# Iot_switch.net
KiCad netlist of a schematic drawn in Altium Designer
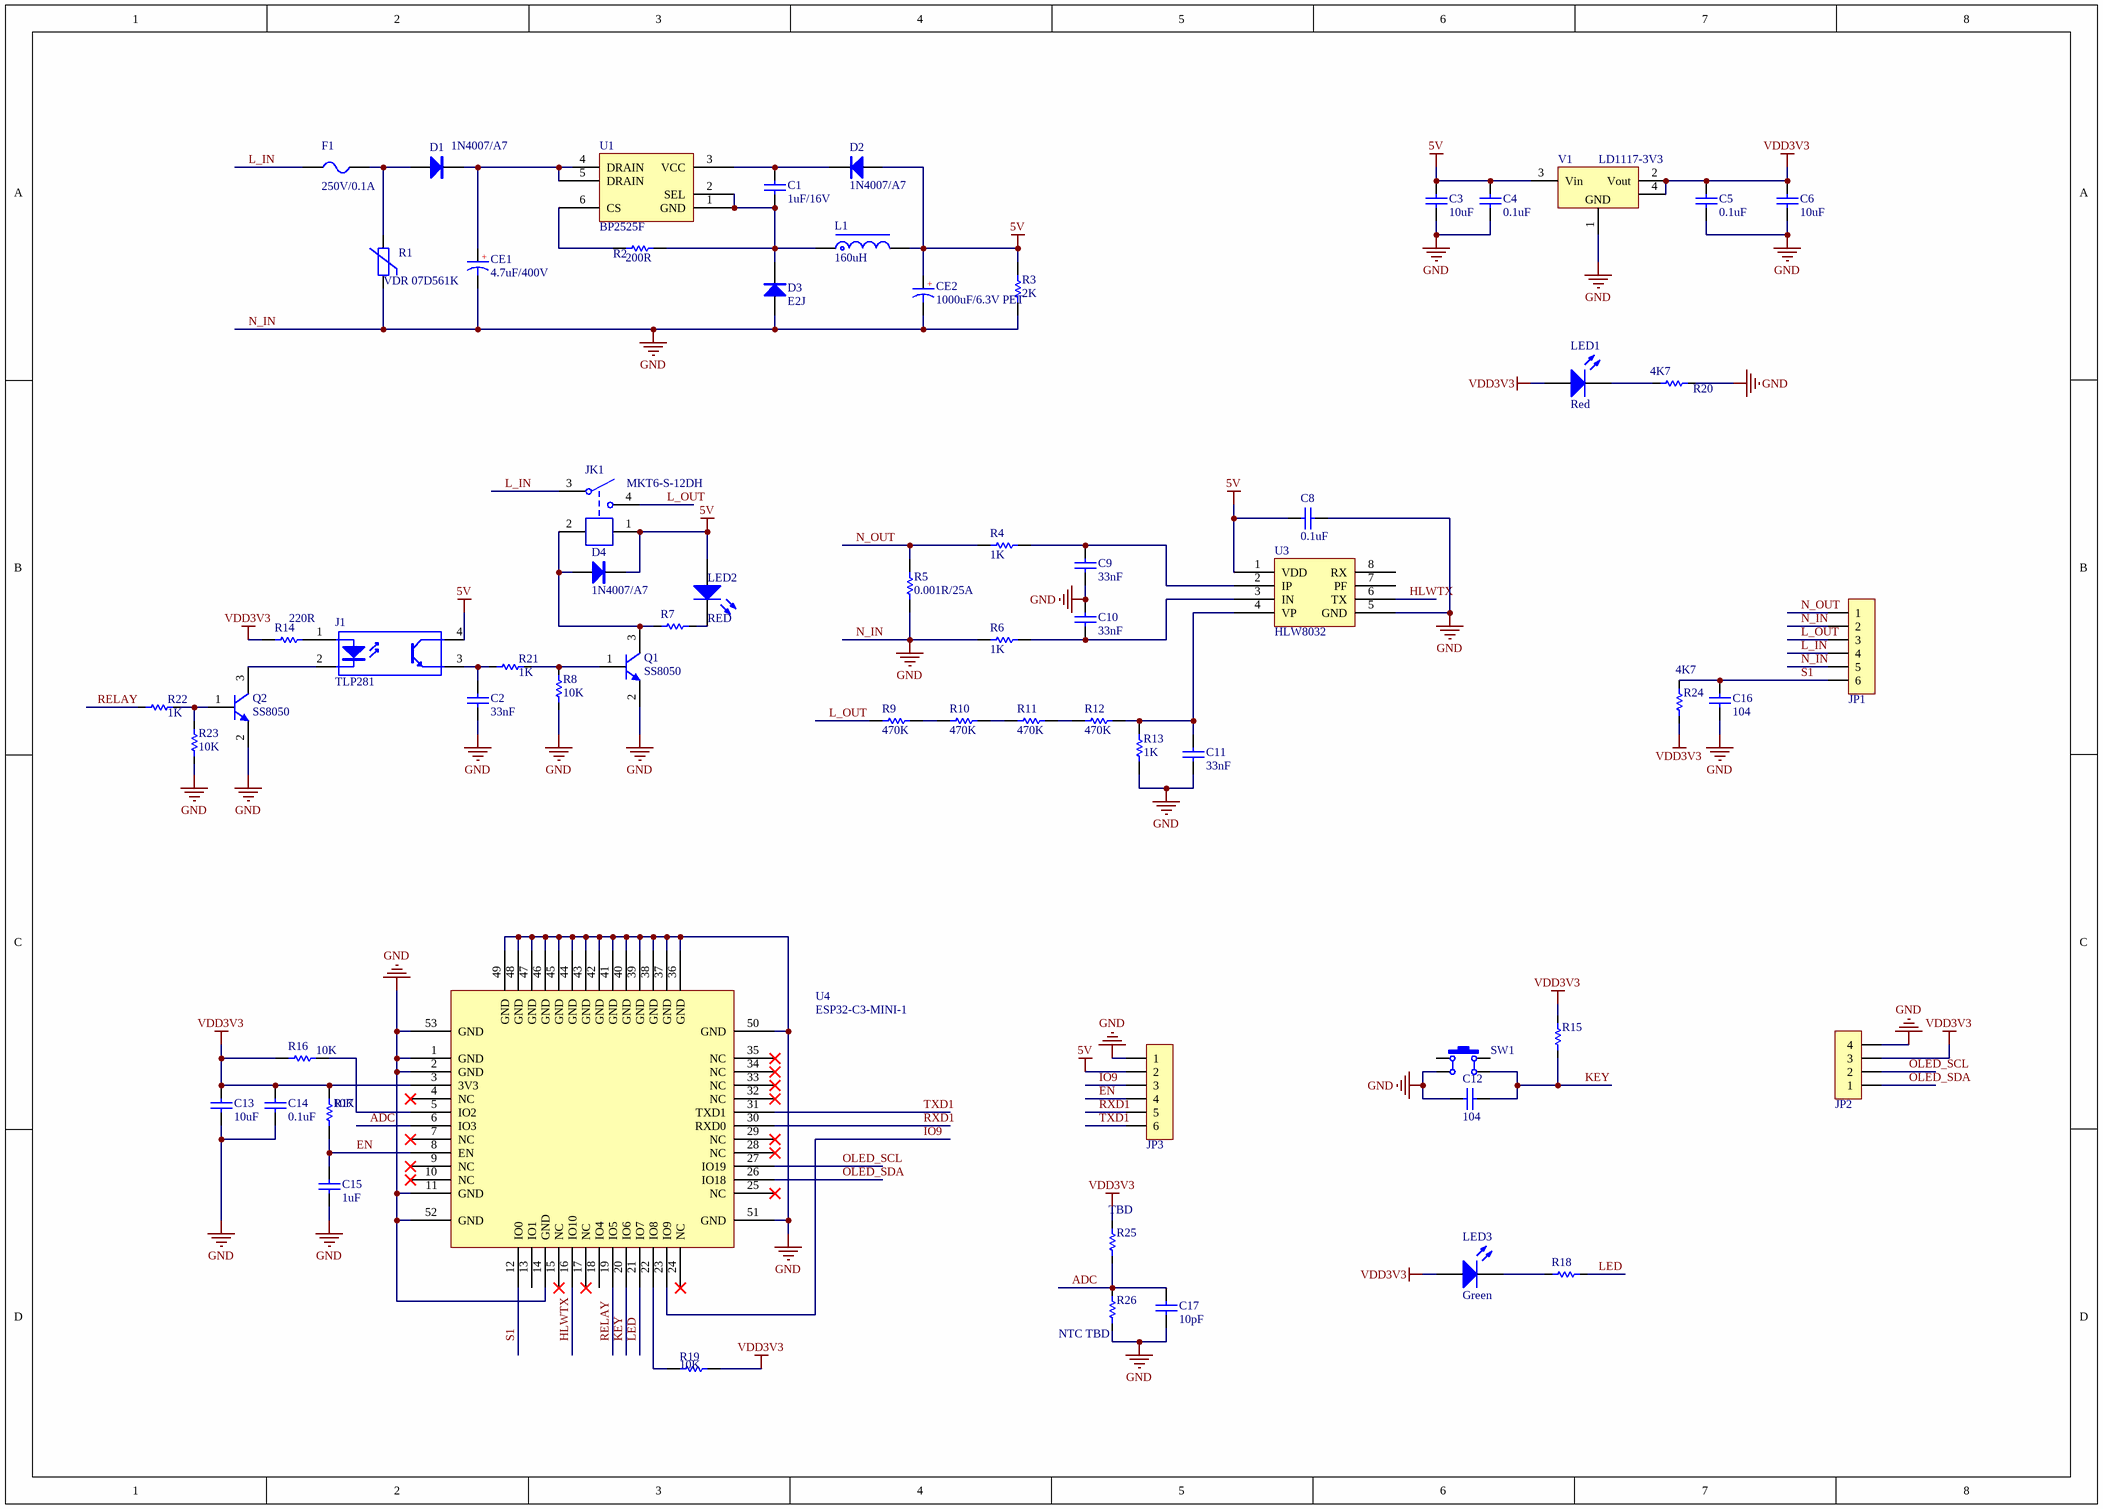
[diagram p0: Iot_switch.SchDoc]

(export (version "E")
  (design (tool "Eeschema 10.0.6"))
  (components
    (comp (ref "C1")
      (value "1uF/16V")
      (footprint "C0805_L")
      (fields (field (name "PUBLISHER") "Altium Limited"))
      (libsource (lib "Miscellaneous Devices") (part "Cap"))
    )
    (comp (ref "C2")
      (value "33nF")
      (footprint "C0603_L")
      (description "贴片电容/MLCC电容")
      (libsource (lib "0.1 - 电阻-电容-电感-保险丝-晶振-晶体-磁珠-电位器-法拉电容-馈通电容") (part "C"))
    )
    (comp (ref "C3")
      (value "10uF")
      (footprint "C0603_L")
      (description "贴片电容/MLCC电容")
      (libsource (lib "0.1 - 电阻-电容-电感-保险丝-晶振-晶体-磁珠-电位器-法拉电容-馈通电容") (part "C"))
    )
    (comp (ref "C4")
      (value "0.1uF")
      (footprint "C0603_L")
      (description "贴片电容/MLCC电容")
      (libsource (lib "0.1 - 电阻-电容-电感-保险丝-晶振-晶体-磁珠-电位器-法拉电容-馈通电容") (part "C"))
    )
    (comp (ref "C5")
      (value "0.1uF")
      (footprint "C0603_L")
      (description "贴片电容/MLCC电容")
      (libsource (lib "0.1 - 电阻-电容-电感-保险丝-晶振-晶体-磁珠-电位器-法拉电容-馈通电容") (part "C"))
    )
    (comp (ref "C6")
      (value "10uF")
      (footprint "C0603_L")
      (description "贴片电容/MLCC电容")
      (libsource (lib "0.1 - 电阻-电容-电感-保险丝-晶振-晶体-磁珠-电位器-法拉电容-馈通电容") (part "C"))
    )
    (comp (ref "C8")
      (value "0.1uF")
      (footprint "C0603_L")
      (description "贴片电容/MLCC电容")
      (libsource (lib "0.1 - 电阻-电容-电感-保险丝-晶振-晶体-磁珠-电位器-法拉电容-馈通电容") (part "C"))
    )
    (comp (ref "C9")
      (value "33nF")
      (footprint "C0603_L")
      (description "贴片电容/MLCC电容")
      (libsource (lib "0.1 - 电阻-电容-电感-保险丝-晶振-晶体-磁珠-电位器-法拉电容-馈通电容") (part "C"))
    )
    (comp (ref "C10")
      (value "33nF")
      (footprint "C0603_L")
      (description "贴片电容/MLCC电容")
      (libsource (lib "0.1 - 电阻-电容-电感-保险丝-晶振-晶体-磁珠-电位器-法拉电容-馈通电容") (part "C"))
    )
    (comp (ref "C11")
      (value "33nF")
      (footprint "C0805_L")
      (description "贴片电容/MLCC电容")
      (libsource (lib "0.1 - 电阻-电容-电感-保险丝-晶振-晶体-磁珠-电位器-法拉电容-馈通电容") (part "C"))
    )
    (comp (ref "C12")
      (value "104")
      (footprint "C0603_L")
      (description "贴片电容/MLCC电容")
      (libsource (lib "0.1 - 电阻-电容-电感-保险丝-晶振-晶体-磁珠-电位器-法拉电容-馈通电容") (part "C"))
    )
    (comp (ref "C13")
      (value "10uF")
      (footprint "C0603_L")
      (description "贴片电容/MLCC电容")
      (libsource (lib "0.1 - 电阻-电容-电感-保险丝-晶振-晶体-磁珠-电位器-法拉电容-馈通电容") (part "C"))
    )
    (comp (ref "C14")
      (value "0.1uF")
      (footprint "C0603_L")
      (description "贴片电容/MLCC电容")
      (libsource (lib "0.1 - 电阻-电容-电感-保险丝-晶振-晶体-磁珠-电位器-法拉电容-馈通电容") (part "C"))
    )
    (comp (ref "C15")
      (value "1uF")
      (footprint "C0603_L")
      (description "贴片电容/MLCC电容")
      (libsource (lib "0.1 - 电阻-电容-电感-保险丝-晶振-晶体-磁珠-电位器-法拉电容-馈通电容") (part "C"))
    )
    (comp (ref "C16")
      (value "104")
      (footprint "C0603_L")
      (description "贴片电容/MLCC电容")
      (libsource (lib "0.1 - 电阻-电容-电感-保险丝-晶振-晶体-磁珠-电位器-法拉电容-馈通电容") (part "C"))
    )
    (comp (ref "C17")
      (value "10pF")
      (footprint "C0603_L")
      (description "贴片电容/MLCC电容")
      (libsource (lib "0.1 - 电阻-电容-电感-保险丝-晶振-晶体-磁珠-电位器-法拉电容-馈通电容") (part "C"))
    )
    (comp (ref "CE1")
      (value "4.7uF/400V")
      (footprint "CE-3.5*8*11.5")
      (description "直插电解电容")
      (libsource (lib "0.1 - 电阻-电容-电感-保险丝-晶振-晶体-磁珠-电位器-法拉电容-馈通电容") (part "CE"))
    )
    (comp (ref "CE2")
      (value "1000uF/6.3V PET")
      (footprint "CE-3.5*8*11.5")
      (description "直插电解电容")
      (libsource (lib "0.1 - 电阻-电容-电感-保险丝-晶振-晶体-磁珠-电位器-法拉电容-馈通电容") (part "CE"))
    )
    (comp (ref "D1")
      (value "1N4007/A7")
      (footprint "SOD-123")
      (description "整流二极管")
      (libsource (lib "0.2 - 二极管-TVS-ESD-整流桥-放电管") (part "1N4007"))
    )
    (comp (ref "D2")
      (value "1N4007/A7")
      (footprint "SOD-123")
      (description "整流二极管")
      (libsource (lib "0.2 - 二极管-TVS-ESD-整流桥-放电管") (part "1N4007"))
    )
    (comp (ref "D3")
      (value "E2J")
      (footprint "SOD-123")
      (description "整流二极管")
      (libsource (lib "0.2 - 二极管-TVS-ESD-整流桥-放电管") (part "1N4007"))
    )
    (comp (ref "D4")
      (value "1N4007/A7")
      (footprint "SOD-123")
      (description "整流二极管")
      (libsource (lib "0.2 - 二极管-TVS-ESD-整流桥-放电管") (part "1N4007"))
    )
    (comp (ref "F1")
      (value "250V/0.1A")
      (footprint "FUSE 4x16_V")
      (description "4*16保险丝")
      (libsource (lib "0.1 - 电阻-电容-电感-保险丝-晶振-晶体-磁珠-电位器-法拉电容-馈通电容") (part "FUSE-4x16"))
    )
    (comp (ref "J1")
      (value "TLP281")
      (footprint "SOP4")
      (description "光耦")
      (libsource (lib "0.3 - LED发光二极管-IR二极管_接收管-光耦") (part "TLP281"))
    )
    (comp (ref "JK1")
      (value "MKT6-S-12DH")
      (footprint "MKT6-S-12DH")
      (description "12V一组常开")
      (libsource (lib "1.4 - 继电器-变压器") (part "MKT6-S-12DH"))
    )
    (comp (ref "JP1")
      (value "HDR-1X6")
      (footprint "KF128-5.08-6P")
      (description "6P接插件")
      (libsource (lib "6.1 - 5.08mm连接器(KF128-KF2EDGK-KF2EDGVHM-5.08)") (part "Header 6"))
    )
    (comp (ref "JP2")
      (value "HDR-1X4")
      (footprint "HDR2.54-M-LI-4P")
      (description "4P接插件")
      (libsource (lib "5.5 - 2.54mm连接器(KF2EDGK_XH2.54_2.54排针排母)") (part "Header 4"))
    )
    (comp (ref "JP3")
      (value "HDR-1X6")
      (footprint "HDR2.54-LI-6P")
      (description "6P接插件")
      (libsource (lib "5.5 - 2.54mm连接器(KF2EDGK_XH2.54_2.54排针排母)") (part "Header 6"))
    )
    (comp (ref "L1")
      (value "160uH")
      (footprint "PK0608")
      (description "工字电感")
      (libsource (lib "0.1 - 电阻-电容-电感-保险丝-晶振-晶体-磁珠-电位器-法拉电容-馈通电容") (part "L-PK"))
    )
    (comp (ref "LED1")
      (value "Red")
      (footprint "LED0603_R")
      (description "贴片LED")
      (libsource (lib "0.3 - LED发光二极管-IR二极管_接收管-光耦") (part "LED"))
    )
    (comp (ref "LED2")
      (value "RED")
      (footprint "LED0603_R")
      (description "贴片LED")
      (libsource (lib "0.3 - LED发光二极管-IR二极管_接收管-光耦") (part "LED"))
    )
    (comp (ref "LED3")
      (value "Green")
      (footprint "LED0603_G")
      (description "贴片LED")
      (libsource (lib "0.3 - LED发光二极管-IR二极管_接收管-光耦") (part "LED"))
    )
    (comp (ref "Q1")
      (value "SS8050")
      (footprint "SOT23-3M")
      (description "NPN三极管")
      (libsource (lib "0.4 - 三极管-场效应管-可控硅") (part "BCP68"))
    )
    (comp (ref "Q2")
      (value "SS8050")
      (footprint "SOT23-3M")
      (description "NPN三极管")
      (libsource (lib "0.4 - 三极管-场效应管-可控硅") (part "BCP68"))
    )
    (comp (ref "R1")
      (value "VDR 07D561K")
      (footprint "VDR 9D-4.5")
      (description "压敏电阻")
      (libsource (lib "0.1 - 电阻-电容-电感-保险丝-晶振-晶体-磁珠-电位器-法拉电容-馈通电容") (part "R_VSR"))
    )
    (comp (ref "R2")
      (value "200R")
      (footprint "R0603_L")
      (description "Resistor")
      (fields (field (name "PUBLISHER") "Altium Limited"))
      (libsource (lib "Miscellaneous Devices") (part "Res1"))
    )
    (comp (ref "R3")
      (value "2K")
      (footprint "R0603_L")
      (description "Resistor")
      (fields (field (name "PUBLISHER") "Altium Limited"))
      (libsource (lib "Miscellaneous Devices") (part "Res1"))
    )
    (comp (ref "R4")
      (value "1K")
      (footprint "R0603_L")
      (description "Resistor")
      (fields (field (name "PUBLISHER") "Altium Limited"))
      (libsource (lib "Miscellaneous Devices") (part "Res1"))
    )
    (comp (ref "R5")
      (value "0.001R/25A")
      (footprint "R2512_L")
      (description "Resistor")
      (fields (field (name "PUBLISHER") "Altium Limited"))
      (libsource (lib "Miscellaneous Devices") (part "Res1"))
    )
    (comp (ref "R6")
      (value "1K")
      (footprint "R0603_L")
      (description "Resistor")
      (fields (field (name "PUBLISHER") "Altium Limited"))
      (libsource (lib "Miscellaneous Devices") (part "Res1"))
    )
    (comp (ref "R7")
      (value "4K7")
      (footprint "R0603_L")
      (description "贴片电阻")
      (fields (field (name "PUBLISHER") "Altium Limited"))
      (libsource (lib "Devices") (part "Res1"))
    )
    (comp (ref "R8")
      (value "10K")
      (footprint "R0603_L")
      (description "贴片电阻")
      (fields (field (name "PUBLISHER") "Altium Limited"))
      (libsource (lib "Devices") (part "Res1"))
    )
    (comp (ref "R9")
      (value "470K")
      (footprint "R0805_L")
      (description "Resistor")
      (fields (field (name "PUBLISHER") "Altium Limited"))
      (libsource (lib "Miscellaneous Devices") (part "Res1"))
    )
    (comp (ref "R10")
      (value "470K")
      (footprint "R0805_L")
      (description "Resistor")
      (fields (field (name "PUBLISHER") "Altium Limited"))
      (libsource (lib "Miscellaneous Devices") (part "Res1"))
    )
    (comp (ref "R11")
      (value "470K")
      (footprint "R0805_L")
      (description "Resistor")
      (fields (field (name "PUBLISHER") "Altium Limited"))
      (libsource (lib "Miscellaneous Devices") (part "Res1"))
    )
    (comp (ref "R12")
      (value "470K")
      (footprint "R0805_L")
      (description "Resistor")
      (fields (field (name "PUBLISHER") "Altium Limited"))
      (libsource (lib "Miscellaneous Devices") (part "Res1"))
    )
    (comp (ref "R13")
      (value "1K")
      (footprint "R0805_l")
      (description "Resistor")
      (fields (field (name "PUBLISHER") "Altium Limited"))
      (libsource (lib "Miscellaneous Devices") (part "Res1"))
    )
    (comp (ref "R14")
      (value "220R")
      (footprint "R0603_l")
      (description "Resistor")
      (fields (field (name "PUBLISHER") "Altium Limited"))
      (libsource (lib "Miscellaneous Devices") (part "Res1"))
    )
    (comp (ref "R15")
      (value "10K")
      (footprint "R0603_L")
      (description "贴片电阻")
      (fields (field (name "PUBLISHER") "Altium Limited"))
      (libsource (lib "Devices") (part "Res1"))
    )
    (comp (ref "R16")
      (value "10K")
      (footprint "R0603_L")
      (description "Resistor")
      (fields (field (name "PUBLISHER") "Altium Limited"))
      (libsource (lib "Miscellaneous Devices") (part "Res1"))
    )
    (comp (ref "R17")
      (value "10K")
      (footprint "R0603_L")
      (description "Resistor")
      (fields (field (name "PUBLISHER") "Altium Limited"))
      (libsource (lib "Miscellaneous Devices") (part "Res1"))
    )
    (comp (ref "R18")
      (value "4K7")
      (footprint "R0603_L")
      (description "贴片电阻")
      (fields (field (name "PUBLISHER") "Altium Limited"))
      (libsource (lib "Devices") (part "Res1"))
    )
    (comp (ref "R19")
      (value "10K")
      (footprint "R0603_L")
      (description "Resistor")
      (fields (field (name "PUBLISHER") "Altium Limited"))
      (libsource (lib "Miscellaneous Devices") (part "Res1"))
    )
    (comp (ref "R20")
      (value "4K7")
      (footprint "R0603_L")
      (description "贴片电阻")
      (fields (field (name "PUBLISHER") "Altium Limited"))
      (libsource (lib "Devices") (part "Res1"))
    )
    (comp (ref "R21")
      (value "1K")
      (footprint "R0603_L")
      (description "贴片电阻")
      (fields (field (name "PUBLISHER") "Altium Limited"))
      (libsource (lib "Devices") (part "Res1"))
    )
    (comp (ref "R22")
      (value "1K")
      (footprint "R0603_L")
      (description "贴片电阻")
      (fields (field (name "PUBLISHER") "Altium Limited"))
      (libsource (lib "Devices") (part "Res1"))
    )
    (comp (ref "R23")
      (value "10K")
      (footprint "R0603_L")
      (description "贴片电阻")
      (fields (field (name "PUBLISHER") "Altium Limited"))
      (libsource (lib "Devices") (part "Res1"))
    )
    (comp (ref "R24")
      (value "4K7")
      (footprint "R0603_L")
      (description "贴片电阻")
      (fields (field (name "PUBLISHER") "Altium Limited"))
      (libsource (lib "Devices") (part "Res1"))
    )
    (comp (ref "R25")
      (value "TBD")
      (footprint "R0603_L")
      (description "贴片电阻")
      (fields (field (name "PUBLISHER") "Altium Limited"))
      (libsource (lib "Devices") (part "Res1"))
    )
    (comp (ref "R26")
      (value "NTC TBD")
      (footprint "R0603_L")
      (description "贴片电阻")
      (fields (field (name "PUBLISHER") "Altium Limited"))
      (libsource (lib "Devices") (part "Res1"))
    )
    (comp (ref "SW1")
      (value "3*4*2.5")
      (footprint "SW-SMD-4.2x3.2_4P")
      (description "贴片4脚轻触开关")
      (libsource (lib "0.5 - 按键_开关_蜂鸣器_电池_测试点_Mark点_铜柱") (part "SW SMD-3*4*2.5"))
    )
    (comp (ref "U1") (value "BP2525F") (footprint "SOT33-5") (libsource (lib "iot switch") (part "BP2525X")))
    (comp (ref "U3") (value "HLW8032") (footprint "SOP_8") (libsource (lib "iot switch") (part "HLW8032")))
    (comp (ref "U4")
      (value "ESP32-C3-MINI-1")
      (footprint "ESP32-C3-MINI-1")
      (libsource (lib "iot switch") (part "ESP32-C3-MINI-1"))
    )
    (comp (ref "V1")
      (value "LD1117-3V3")
      (footprint "SOT223_L")
      (description "三端稳压芯片")
      (libsource (lib "0.7 - 电源类芯片") (part "LD1117"))
    )
  )
  (nets
    (net (code "1") (name "/ADC") (class "Default")
      (node (ref "C17") (pin "1") (pinfunction "1_1") (pintype "passive"))
      (node (ref "R25") (pin "1") (pinfunction "TOP_1") (pintype "passive"))
      (node (ref "R26") (pin "2") (pinfunction "BOT_2") (pintype "passive"))
      (node (ref "U4") (pin "6") (pinfunction "IO3_6") (pintype "passive"))
    )
    (net (code "2") (name "/EN") (class "Default")
      (node (ref "C15") (pin "2") (pinfunction "2_2") (pintype "passive"))
      (node (ref "JP3") (pin "4") (pinfunction "4_4") (pintype "passive"))
      (node (ref "R17") (pin "1") (pinfunction "1_1") (pintype "passive"))
      (node (ref "U4") (pin "8") (pinfunction "EN_8") (pintype "passive"))
    )
    (net (code "3") (name "/HLWTX") (class "Default")
      (node (ref "U3") (pin "6") (pinfunction "TX_6") (pintype "passive"))
      (node (ref "U4") (pin "16") (pinfunction "IO10_16") (pintype "passive"))
    )
    (net (code "4") (name "/IO9") (class "Default")
      (node (ref "JP3") (pin "3") (pinfunction "3_3") (pintype "passive"))
      (node (ref "U4") (pin "23") (pinfunction "IO9_23") (pintype "passive"))
    )
    (net (code "5") (name "/KEY") (class "Default")
      (node (ref "C12") (pin "2") (pinfunction "2_2") (pintype "passive"))
      (node (ref "R15") (pin "1") (pinfunction "TOP_1") (pintype "passive"))
      (node (ref "SW1") (pin "3") (pinfunction "3_3") (pintype "passive"))
      (node (ref "U4") (pin "20") (pinfunction "IO6_20") (pintype "passive"))
    )
    (net (code "6") (name "/LED") (class "Default")
      (node (ref "R18") (pin "2") (pinfunction "BOT_2") (pintype "passive"))
      (node (ref "U4") (pin "21") (pinfunction "IO7_21") (pintype "passive"))
    )
    (net (code "7") (name "/L_IN") (class "Default")
      (node (ref "F1") (pin "2") (pinfunction "2_2") (pintype "passive"))
      (node (ref "JK1") (pin "3") (pinfunction "3_3") (pintype "passive"))
      (node (ref "JP1") (pin "4") (pinfunction "4_4") (pintype "passive"))
    )
    (net (code "8") (name "/L_OUT") (class "Default")
      (node (ref "JK1") (pin "4") (pinfunction "4_4") (pintype "passive"))
      (node (ref "JP1") (pin "3") (pinfunction "3_3") (pintype "passive"))
      (node (ref "R9") (pin "2") (pinfunction "2_2") (pintype "passive"))
    )
    (net (code "9") (name "/N_OUT") (class "Default")
      (node (ref "JP1") (pin "1") (pinfunction "1_1") (pintype "passive"))
      (node (ref "R4") (pin "2") (pinfunction "2_2") (pintype "passive"))
      (node (ref "R5") (pin "1") (pinfunction "1_1") (pintype "passive"))
    )
    (net (code "10") (name "/OLED_SCL") (class "Default")
      (node (ref "JP2") (pin "2") (pinfunction "2_2") (pintype "passive"))
      (node (ref "U4") (pin "27") (pinfunction "IO19_27") (pintype "passive"))
    )
    (net (code "11") (name "/OLED_SDA") (class "Default")
      (node (ref "JP2") (pin "1") (pinfunction "1_1") (pintype "passive"))
      (node (ref "U4") (pin "26") (pinfunction "IO18_26") (pintype "passive"))
    )
    (net (code "12") (name "/RELAY") (class "Default")
      (node (ref "R22") (pin "1") (pinfunction "TOP_1") (pintype "passive"))
      (node (ref "U4") (pin "19") (pinfunction "IO5_19") (pintype "passive"))
    )
    (net (code "13") (name "/RXD1") (class "Default")
      (node (ref "JP3") (pin "5") (pinfunction "5_5") (pintype "passive"))
      (node (ref "U4") (pin "30") (pinfunction "RXD0_30") (pintype "passive"))
    )
    (net (code "14") (name "/S1") (class "Default")
      (node (ref "C16") (pin "2") (pinfunction "2_2") (pintype "passive"))
      (node (ref "JP1") (pin "6") (pinfunction "6_6") (pintype "passive"))
      (node (ref "R24") (pin "2") (pinfunction "BOT_2") (pintype "passive"))
      (node (ref "U4") (pin "12") (pinfunction "IO0_12") (pintype "passive"))
    )
    (net (code "15") (name "/TXD1") (class "Default")
      (node (ref "JP3") (pin "6") (pinfunction "6_6") (pintype "passive"))
      (node (ref "U4") (pin "31") (pinfunction "TXD1_31") (pintype "passive"))
    )
    (net (code "16") (name "5V") (class "Default")
      (node (ref "C3") (pin "2") (pinfunction "2_2") (pintype "passive"))
      (node (ref "C4") (pin "2") (pinfunction "2_2") (pintype "passive"))
      (node (ref "C8") (pin "2") (pinfunction "2_2") (pintype "passive"))
      (node (ref "CE2") (pin "1") (pinfunction "1_1") (pintype "passive"))
      (node (ref "D2") (pin "1") (pinfunction "A_1") (pintype "passive"))
      (node (ref "D4") (pin "2") (pinfunction "K_2") (pintype "passive"))
      (node (ref "J1") (pin "4") (pinfunction "C_4") (pintype "passive"))
      (node (ref "JK1") (pin "1") (pinfunction "1_1") (pintype "passive"))
      (node (ref "JP3") (pin "2") (pinfunction "2_2") (pintype "passive"))
      (node (ref "L1") (pin "2") (pinfunction "2_2") (pintype "passive"))
      (node (ref "LED2") (pin "1") (pinfunction "A_1") (pintype "passive"))
      (node (ref "R3") (pin "2") (pinfunction "2_2") (pintype "passive"))
      (node (ref "U3") (pin "1") (pinfunction "VDD_1") (pintype "passive"))
      (node (ref "V1") (pin "3") (pinfunction "Vin_3") (pintype "passive"))
    )
    (net (code "17") (name "GND") (class "Default")
      (node (ref "C10") (pin "1") (pinfunction "1_1") (pintype "passive"))
      (node (ref "C11") (pin "2") (pinfunction "2_2") (pintype "passive"))
      (node (ref "C12") (pin "1") (pinfunction "1_1") (pintype "passive"))
      (node (ref "C13") (pin "1") (pinfunction "1_1") (pintype "passive"))
      (node (ref "C14") (pin "1") (pinfunction "1_1") (pintype "passive"))
      (node (ref "C15") (pin "1") (pinfunction "1_1") (pintype "passive"))
      (node (ref "C16") (pin "1") (pinfunction "1_1") (pintype "passive"))
      (node (ref "C17") (pin "2") (pinfunction "2_2") (pintype "passive"))
      (node (ref "C2") (pin "2") (pinfunction "2_2") (pintype "passive"))
      (node (ref "C3") (pin "1") (pinfunction "1_1") (pintype "passive"))
      (node (ref "C4") (pin "1") (pinfunction "1_1") (pintype "passive"))
      (node (ref "C5") (pin "1") (pinfunction "1_1") (pintype "passive"))
      (node (ref "C6") (pin "1") (pinfunction "1_1") (pintype "passive"))
      (node (ref "C8") (pin "1") (pinfunction "1_1") (pintype "passive"))
      (node (ref "C9") (pin "2") (pinfunction "2_2") (pintype "passive"))
      (node (ref "CE1") (pin "2") (pinfunction "2_2") (pintype "passive"))
      (node (ref "CE2") (pin "2") (pinfunction "2_2") (pintype "passive"))
      (node (ref "D3") (pin "1") (pinfunction "A_1") (pintype "passive"))
      (node (ref "JP1") (pin "2") (pinfunction "2_2") (pintype "passive"))
      (node (ref "JP1") (pin "5") (pinfunction "5_5") (pintype "passive"))
      (node (ref "JP2") (pin "4") (pinfunction "4_4") (pintype "passive"))
      (node (ref "JP3") (pin "1") (pinfunction "1_1") (pintype "passive"))
      (node (ref "Q1") (pin "2") (pinfunction "E_2") (pintype "passive"))
      (node (ref "Q2") (pin "2") (pinfunction "E_2") (pintype "passive"))
      (node (ref "R1") (pin "1") (pinfunction "1_1") (pintype "passive"))
      (node (ref "R13") (pin "2") (pinfunction "2_2") (pintype "passive"))
      (node (ref "R20") (pin "2") (pinfunction "BOT_2") (pintype "passive"))
      (node (ref "R23") (pin "2") (pinfunction "BOT_2") (pintype "passive"))
      (node (ref "R26") (pin "1") (pinfunction "TOP_1") (pintype "passive"))
      (node (ref "R3") (pin "1") (pinfunction "1_1") (pintype "passive"))
      (node (ref "R5") (pin "2") (pinfunction "2_2") (pintype "passive"))
      (node (ref "R6") (pin "2") (pinfunction "2_2") (pintype "passive"))
      (node (ref "R8") (pin "2") (pinfunction "BOT_2") (pintype "passive"))
      (node (ref "SW1") (pin "4") (pinfunction "4_4") (pintype "passive"))
      (node (ref "U3") (pin "5") (pinfunction "GND_5") (pintype "passive"))
      (node (ref "U4") (pin "1") (pinfunction "GND_1") (pintype "passive"))
      (node (ref "U4") (pin "11") (pinfunction "GND_11") (pintype "passive"))
      (node (ref "U4") (pin "14") (pinfunction "GND_14") (pintype "passive"))
      (node (ref "U4") (pin "2") (pinfunction "GND_2") (pintype "passive"))
      (node (ref "U4") (pin "36") (pinfunction "GND_36") (pintype "passive"))
      (node (ref "U4") (pin "37") (pinfunction "GND_37") (pintype "passive"))
      (node (ref "U4") (pin "38") (pinfunction "GND_38") (pintype "passive"))
      (node (ref "U4") (pin "39") (pinfunction "GND_39") (pintype "passive"))
      (node (ref "U4") (pin "40") (pinfunction "GND_40") (pintype "passive"))
      (node (ref "U4") (pin "41") (pinfunction "GND_41") (pintype "passive"))
      (node (ref "U4") (pin "42") (pinfunction "GND_42") (pintype "passive"))
      (node (ref "U4") (pin "43") (pinfunction "GND_43") (pintype "passive"))
      (node (ref "U4") (pin "44") (pinfunction "GND_44") (pintype "passive"))
      (node (ref "U4") (pin "45") (pinfunction "GND_45") (pintype "passive"))
      (node (ref "U4") (pin "46") (pinfunction "GND_46") (pintype "passive"))
      (node (ref "U4") (pin "47") (pinfunction "GND_47") (pintype "passive"))
      (node (ref "U4") (pin "48") (pinfunction "GND_48") (pintype "passive"))
      (node (ref "U4") (pin "49") (pinfunction "GND_49") (pintype "passive"))
      (node (ref "U4") (pin "50") (pinfunction "GND_50") (pintype "passive"))
      (node (ref "U4") (pin "51") (pinfunction "GND_51") (pintype "passive"))
      (node (ref "U4") (pin "52") (pinfunction "GND_52") (pintype "passive"))
      (node (ref "U4") (pin "53") (pinfunction "GND_53") (pintype "passive"))
      (node (ref "V1") (pin "1") (pinfunction "GND_1") (pintype "passive"))
    )
    (net (code "18") (name "Net-(D1-A)") (class "Default")
      (node (ref "D1") (pin "1") (pinfunction "A_1") (pintype "passive"))
      (node (ref "F1") (pin "1") (pinfunction "1_1") (pintype "passive"))
      (node (ref "R1") (pin "2") (pinfunction "2_2") (pintype "passive"))
    )
    (net (code "19") (name "Net-(D1-K)") (class "Default")
      (node (ref "CE1") (pin "1") (pinfunction "1_1") (pintype "passive"))
      (node (ref "D1") (pin "2") (pinfunction "K_2") (pintype "passive"))
      (node (ref "U1") (pin "4") (pinfunction "DRAIN_4") (pintype "passive"))
      (node (ref "U1") (pin "5") (pinfunction "DRAIN_5") (pintype "passive"))
    )
    (net (code "20") (name "Net-(D2-K)") (class "Default")
      (node (ref "C1") (pin "2") (pinfunction "2_2") (pintype "passive"))
      (node (ref "D2") (pin "2") (pinfunction "K_2") (pintype "passive"))
      (node (ref "U1") (pin "3") (pinfunction "VCC_3") (pintype "passive"))
    )
    (net (code "21") (name "Net-(D3-K)") (class "Default")
      (node (ref "C1") (pin "1") (pinfunction "1_1") (pintype "passive"))
      (node (ref "D3") (pin "2") (pinfunction "K_2") (pintype "passive"))
      (node (ref "L1") (pin "1") (pinfunction "1_1") (pintype "passive"))
      (node (ref "R2") (pin "1") (pinfunction "1_1") (pintype "passive"))
      (node (ref "U1") (pin "1") (pinfunction "GND_1") (pintype "passive"))
      (node (ref "U1") (pin "2") (pinfunction "SEL_2") (pintype "passive"))
    )
    (net (code "22") (name "Net-(D4-A)") (class "Default")
      (node (ref "D4") (pin "1") (pinfunction "A_1") (pintype "passive"))
      (node (ref "JK1") (pin "2") (pinfunction "2_2") (pintype "passive"))
      (node (ref "Q1") (pin "3") (pinfunction "C_3") (pintype "passive"))
      (node (ref "R7") (pin "2") (pinfunction "BOT_2") (pintype "passive"))
    )
    (net (code "23") (name "Net-(J1-A)") (class "Default")
      (node (ref "J1") (pin "1") (pinfunction "A_1") (pintype "passive"))
      (node (ref "R14") (pin "2") (pinfunction "2_2") (pintype "passive"))
    )
    (net (code "24") (name "Net-(J1-E)") (class "Default")
      (node (ref "C2") (pin "1") (pinfunction "1_1") (pintype "passive"))
      (node (ref "J1") (pin "3") (pinfunction "E_3") (pintype "passive"))
      (node (ref "R21") (pin "1") (pinfunction "TOP_1") (pintype "passive"))
    )
    (net (code "25") (name "Net-(J1-K)") (class "Default")
      (node (ref "J1") (pin "2") (pinfunction "K_2") (pintype "passive"))
      (node (ref "Q2") (pin "3") (pinfunction "C_3") (pintype "passive"))
    )
    (net (code "26") (name "Net-(LED1-K)") (class "Default")
      (node (ref "LED1") (pin "2") (pinfunction "K_2") (pintype "passive"))
      (node (ref "R20") (pin "1") (pinfunction "TOP_1") (pintype "passive"))
    )
    (net (code "27") (name "Net-(LED2-K)") (class "Default")
      (node (ref "LED2") (pin "2") (pinfunction "K_2") (pintype "passive"))
      (node (ref "R7") (pin "1") (pinfunction "TOP_1") (pintype "passive"))
    )
    (net (code "28") (name "Net-(LED3-K)") (class "Default")
      (node (ref "LED3") (pin "2") (pinfunction "K_2") (pintype "passive"))
      (node (ref "R18") (pin "1") (pinfunction "TOP_1") (pintype "passive"))
    )
    (net (code "29") (name "Net-(Q1-B)") (class "Default")
      (node (ref "Q1") (pin "1") (pinfunction "B_1") (pintype "passive"))
      (node (ref "R21") (pin "2") (pinfunction "BOT_2") (pintype "passive"))
      (node (ref "R8") (pin "1") (pinfunction "TOP_1") (pintype "passive"))
    )
    (net (code "30") (name "Net-(Q2-B)") (class "Default")
      (node (ref "Q2") (pin "1") (pinfunction "B_1") (pintype "passive"))
      (node (ref "R22") (pin "2") (pinfunction "BOT_2") (pintype "passive"))
      (node (ref "R23") (pin "1") (pinfunction "TOP_1") (pintype "passive"))
    )
    (net (code "31") (name "Net-(R10-Pad1)") (class "Default")
      (node (ref "R10") (pin "1") (pinfunction "1_1") (pintype "passive"))
      (node (ref "R11") (pin "2") (pinfunction "2_2") (pintype "passive"))
    )
    (net (code "32") (name "Net-(R10-Pad2)") (class "Default")
      (node (ref "R10") (pin "2") (pinfunction "2_2") (pintype "passive"))
      (node (ref "R9") (pin "1") (pinfunction "1_1") (pintype "passive"))
    )
    (net (code "33") (name "Net-(R11-Pad1)") (class "Default")
      (node (ref "R11") (pin "1") (pinfunction "1_1") (pintype "passive"))
      (node (ref "R12") (pin "2") (pinfunction "2_2") (pintype "passive"))
    )
    (net (code "34") (name "Net-(U1-CS)") (class "Default")
      (node (ref "R2") (pin "2") (pinfunction "2_2") (pintype "passive"))
      (node (ref "U1") (pin "6") (pinfunction "CS_6") (pintype "passive"))
    )
    (net (code "35") (name "Net-(U3-IN)") (class "Default")
      (node (ref "C10") (pin "2") (pinfunction "2_2") (pintype "passive"))
      (node (ref "R6") (pin "1") (pinfunction "1_1") (pintype "passive"))
      (node (ref "U3") (pin "3") (pinfunction "IN_3") (pintype "passive"))
    )
    (net (code "36") (name "Net-(U3-IP)") (class "Default")
      (node (ref "C9") (pin "1") (pinfunction "1_1") (pintype "passive"))
      (node (ref "R4") (pin "1") (pinfunction "1_1") (pintype "passive"))
      (node (ref "U3") (pin "2") (pinfunction "IP_2") (pintype "passive"))
    )
    (net (code "37") (name "Net-(U3-VP)") (class "Default")
      (node (ref "C11") (pin "1") (pinfunction "1_1") (pintype "passive"))
      (node (ref "R12") (pin "1") (pinfunction "1_1") (pintype "passive"))
      (node (ref "R13") (pin "1") (pinfunction "1_1") (pintype "passive"))
      (node (ref "U3") (pin "4") (pinfunction "VP_4") (pintype "passive"))
    )
    (net (code "38") (name "Net-(U4-IO2)") (class "Default")
      (node (ref "R16") (pin "2") (pinfunction "2_2") (pintype "passive"))
      (node (ref "U4") (pin "5") (pinfunction "IO2_5") (pintype "passive"))
    )
    (net (code "39") (name "Net-(U4-IO8)") (class "Default")
      (node (ref "R19") (pin "2") (pinfunction "2_2") (pintype "passive"))
      (node (ref "U4") (pin "22") (pinfunction "IO8_22") (pintype "passive"))
    )
    (net (code "40") (name "VDD3V3") (class "Default")
      (node (ref "C13") (pin "2") (pinfunction "2_2") (pintype "passive"))
      (node (ref "C14") (pin "2") (pinfunction "2_2") (pintype "passive"))
      (node (ref "C5") (pin "2") (pinfunction "2_2") (pintype "passive"))
      (node (ref "C6") (pin "2") (pinfunction "2_2") (pintype "passive"))
      (node (ref "JP2") (pin "3") (pinfunction "3_3") (pintype "passive"))
      (node (ref "LED1") (pin "1") (pinfunction "A_1") (pintype "passive"))
      (node (ref "LED3") (pin "1") (pinfunction "A_1") (pintype "passive"))
      (node (ref "R14") (pin "1") (pinfunction "1_1") (pintype "passive"))
      (node (ref "R15") (pin "2") (pinfunction "BOT_2") (pintype "passive"))
      (node (ref "R16") (pin "1") (pinfunction "1_1") (pintype "passive"))
      (node (ref "R17") (pin "2") (pinfunction "2_2") (pintype "passive"))
      (node (ref "R19") (pin "1") (pinfunction "1_1") (pintype "passive"))
      (node (ref "R24") (pin "1") (pinfunction "TOP_1") (pintype "passive"))
      (node (ref "R25") (pin "2") (pinfunction "BOT_2") (pintype "passive"))
      (node (ref "U4") (pin "3") (pinfunction "3V3_3") (pintype "passive"))
      (node (ref "V1") (pin "2") (pinfunction "Vout_2") (pintype "passive"))
      (node (ref "V1") (pin "4") (pinfunction "OUT_4") (pintype "passive"))
    )
    (net (code "41") (name "unconnected-(SW1-Pad1)") (class "Default")
      (node (ref "SW1") (pin "1") (pinfunction "1_1") (pintype "passive"))
    )
    (net (code "42") (name "unconnected-(SW1-Pad2)") (class "Default")
      (node (ref "SW1") (pin "2") (pinfunction "2_2") (pintype "passive"))
    )
    (net (code "43") (name "unconnected-(U3-PF-Pad7)") (class "Default")
      (node (ref "U3") (pin "7") (pinfunction "PF_7") (pintype "passive"))
    )
    (net (code "44") (name "unconnected-(U3-RX-Pad8)") (class "Default")
      (node (ref "U3") (pin "8") (pinfunction "RX_8") (pintype "passive"))
    )
    (net (code "45") (name "unconnected-(U4-IO1-Pad13)") (class "Default")
      (node (ref "U4") (pin "13") (pinfunction "IO1_13") (pintype "passive"))
    )
    (net (code "46") (name "unconnected-(U4-IO4-Pad18)") (class "Default")
      (node (ref "U4") (pin "18") (pinfunction "IO4_18") (pintype "passive"))
    )
    (net (code "47") (name "unconnected-(U4-NC-Pad4)") (class "Default")
      (node (ref "U4") (pin "4") (pinfunction "NC_4") (pintype "passive+no_connect"))
    )
    (net (code "48") (name "unconnected-(U4-NC-Pad7)") (class "Default")
      (node (ref "U4") (pin "7") (pinfunction "NC_7") (pintype "passive+no_connect"))
    )
    (net (code "49") (name "unconnected-(U4-NC-Pad9)") (class "Default")
      (node (ref "U4") (pin "9") (pinfunction "NC_9") (pintype "passive+no_connect"))
    )
    (net (code "50") (name "unconnected-(U4-NC-Pad10)") (class "Default")
      (node (ref "U4") (pin "10") (pinfunction "NC_10") (pintype "passive+no_connect"))
    )
    (net (code "51") (name "unconnected-(U4-NC-Pad15)") (class "Default")
      (node (ref "U4") (pin "15") (pinfunction "NC_15") (pintype "passive+no_connect"))
    )
    (net (code "52") (name "unconnected-(U4-NC-Pad17)") (class "Default")
      (node (ref "U4") (pin "17") (pinfunction "NC_17") (pintype "passive+no_connect"))
    )
    (net (code "53") (name "unconnected-(U4-NC-Pad24)") (class "Default")
      (node (ref "U4") (pin "24") (pinfunction "NC_24") (pintype "passive+no_connect"))
    )
    (net (code "54") (name "unconnected-(U4-NC-Pad25)") (class "Default")
      (node (ref "U4") (pin "25") (pinfunction "NC_25") (pintype "passive+no_connect"))
    )
    (net (code "55") (name "unconnected-(U4-NC-Pad28)") (class "Default")
      (node (ref "U4") (pin "28") (pinfunction "NC_28") (pintype "passive+no_connect"))
    )
    (net (code "56") (name "unconnected-(U4-NC-Pad29)") (class "Default")
      (node (ref "U4") (pin "29") (pinfunction "NC_29") (pintype "passive+no_connect"))
    )
    (net (code "57") (name "unconnected-(U4-NC-Pad32)") (class "Default")
      (node (ref "U4") (pin "32") (pinfunction "NC_32") (pintype "passive+no_connect"))
    )
    (net (code "58") (name "unconnected-(U4-NC-Pad33)") (class "Default")
      (node (ref "U4") (pin "33") (pinfunction "NC_33") (pintype "passive+no_connect"))
    )
    (net (code "59") (name "unconnected-(U4-NC-Pad34)") (class "Default")
      (node (ref "U4") (pin "34") (pinfunction "NC_34") (pintype "passive+no_connect"))
    )
    (net (code "60") (name "unconnected-(U4-NC-Pad35)") (class "Default")
      (node (ref "U4") (pin "35") (pinfunction "NC_35") (pintype "passive+no_connect"))
    )
  )
)
